# S09_Connectors.net
KiCad netlist of a schematic drawn in Altium Designer
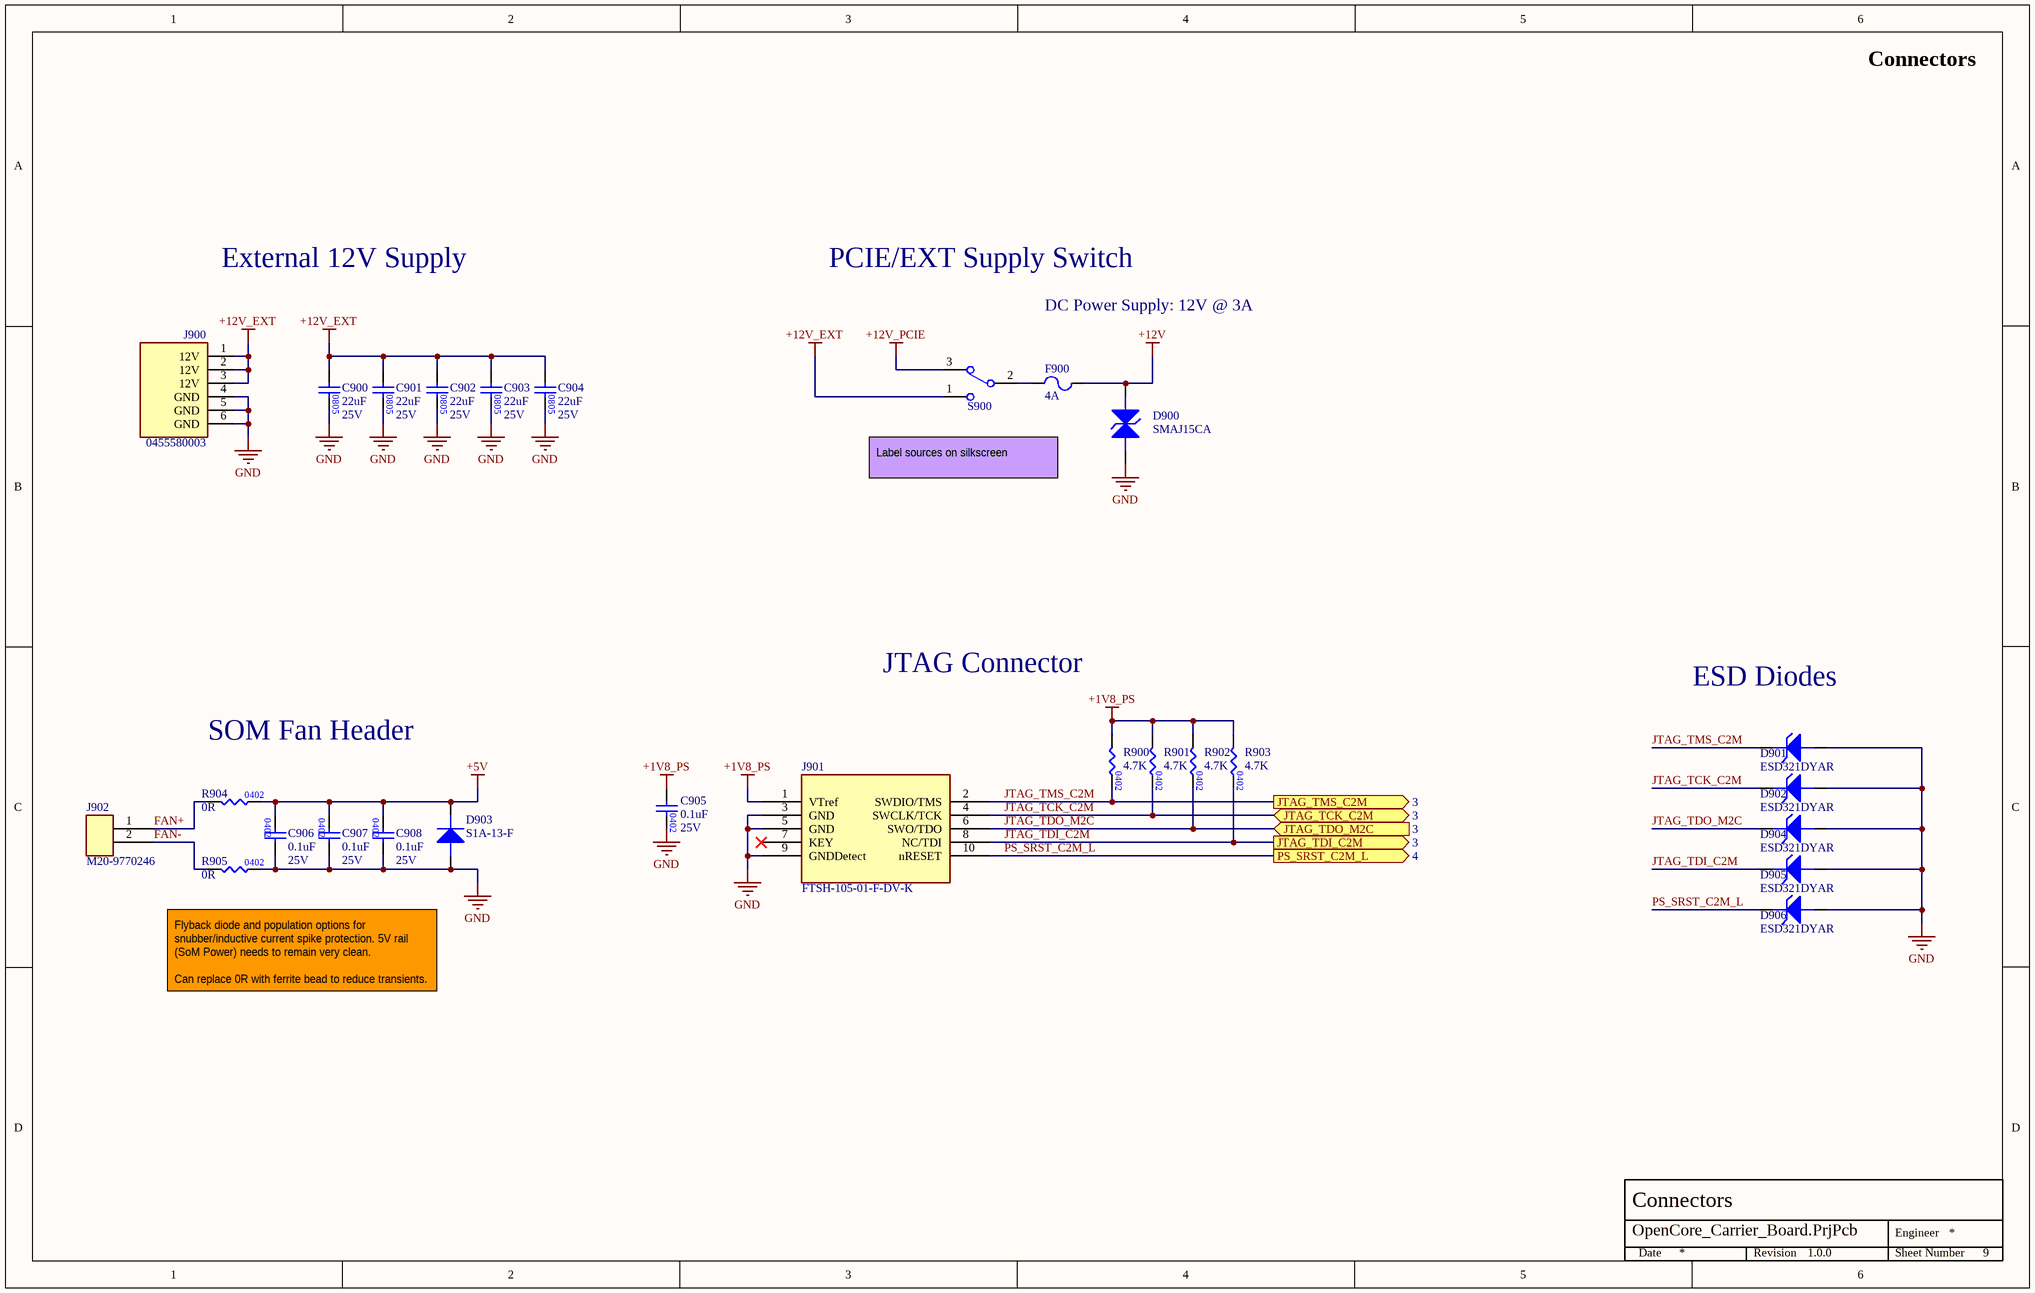
[diagram p0: S09_Connectors.SchDoc]

(export (version "E")
  (design (tool "Eeschema 10.0.6"))
  (components
    (comp (ref "C900")
      (value "22uF")
      (footprint "CAP0805")
      (description "CAP CER 22UF 25V X5R 0805")
      (fields
        (field (name "MANUFACTURER") "Samsung Electro-Mechanics")
        (field (name "TOLERANCE") "20%")
        (field (name "VOLTAGE RATING") "25V")
      )
      (libsource (lib "OpenCore_Sch_Lib") (part "CAP_CL21A226MAYNNNE"))
    )
    (comp (ref "C901")
      (value "22uF")
      (footprint "CAP0805")
      (description "CAP CER 22UF 25V X5R 0805")
      (fields
        (field (name "MANUFACTURER") "Samsung Electro-Mechanics")
        (field (name "TOLERANCE") "20%")
        (field (name "VOLTAGE RATING") "25V")
      )
      (libsource (lib "OpenCore_Sch_Lib") (part "CAP_CL21A226MAYNNNE"))
    )
    (comp (ref "C902")
      (value "22uF")
      (footprint "CAP0805")
      (description "CAP CER 22UF 25V X5R 0805")
      (fields
        (field (name "MANUFACTURER") "Samsung Electro-Mechanics")
        (field (name "TOLERANCE") "20%")
        (field (name "VOLTAGE RATING") "25V")
      )
      (libsource (lib "OpenCore_Sch_Lib") (part "CAP_CL21A226MAYNNNE"))
    )
    (comp (ref "C903")
      (value "22uF")
      (footprint "CAP0805")
      (description "CAP CER 22UF 25V X5R 0805")
      (fields
        (field (name "MANUFACTURER") "Samsung Electro-Mechanics")
        (field (name "TOLERANCE") "20%")
        (field (name "VOLTAGE RATING") "25V")
      )
      (libsource (lib "OpenCore_Sch_Lib") (part "CAP_CL21A226MAYNNNE"))
    )
    (comp (ref "C904")
      (value "22uF")
      (footprint "CAP0805")
      (description "CAP CER 22UF 25V X5R 0805")
      (fields
        (field (name "MANUFACTURER") "Samsung Electro-Mechanics")
        (field (name "TOLERANCE") "20%")
        (field (name "VOLTAGE RATING") "25V")
      )
      (libsource (lib "OpenCore_Sch_Lib") (part "CAP_CL21A226MAYNNNE"))
    )
    (comp (ref "C905")
      (value "0.1uF")
      (footprint "CAP0402")
      (description "CAP CER 0.1UF 25V X5R 0402")
      (fields
        (field (name "MANUFACTURER") "Samsung Electro-Mechanics")
        (field (name "TOLERANCE") "10%")
        (field (name "VOLTAGE RATING") "25V")
      )
      (libsource (lib "OpenCore_Sch_Lib") (part "CAP_CL05A104KA5NNNC"))
    )
    (comp (ref "C906")
      (value "0.1uF")
      (footprint "CAP0402")
      (description "CAP CER 0.1UF 25V X5R 0402")
      (fields
        (field (name "MANUFACTURER") "Samsung Electro-Mechanics")
        (field (name "TOLERANCE") "10%")
        (field (name "VOLTAGE RATING") "25V")
      )
      (libsource (lib "OpenCore_Sch_Lib") (part "CAP_CL05A104KA5NNNC"))
    )
    (comp (ref "C907")
      (value "0.1uF")
      (footprint "CAP0402")
      (description "CAP CER 0.1UF 25V X5R 0402")
      (fields
        (field (name "MANUFACTURER") "Samsung Electro-Mechanics")
        (field (name "TOLERANCE") "10%")
        (field (name "VOLTAGE RATING") "25V")
      )
      (libsource (lib "OpenCore_Sch_Lib") (part "CAP_CL05A104KA5NNNC"))
    )
    (comp (ref "C908")
      (value "0.1uF")
      (footprint "CAP0402")
      (description "CAP CER 0.1UF 25V X5R 0402")
      (fields
        (field (name "MANUFACTURER") "Samsung Electro-Mechanics")
        (field (name "TOLERANCE") "10%")
        (field (name "VOLTAGE RATING") "25V")
      )
      (libsource (lib "OpenCore_Sch_Lib") (part "CAP_CL05A104KA5NNNC"))
    )
    (comp (ref "D900")
      (value "TVS DIODE 15VWM 24.4VC DO214AC")
      (footprint "LITTLEFUSE_DO-2014")
      (description "24.4V Clamp 16.4A Ipp Tvs Diode Surface Mount DO-214AC (SMA)")
      (fields (field (name "MANUFACTURER PART NUMBER") "SMAJ15CA"))
      (libsource (lib "OpenCore_Sch_Lib") (part "SMAJ15CA"))
    )
    (comp (ref "D901")
      (value "ESD321DYAR")
      (footprint "TI_SOD523")
      (description "TVS DIODE 3.6VWM 6.3VC SOT5X3")
      (fields (field (name "MANFACTURER PART NUMBER") "ESD321DYAR"))
      (libsource (lib "OpenCore_Sch_Lib") (part "ESD321DYAR"))
    )
    (comp (ref "D902")
      (value "ESD321DYAR")
      (footprint "TI_SOD523")
      (description "TVS DIODE 3.6VWM 6.3VC SOT5X3")
      (fields (field (name "MANFACTURER PART NUMBER") "ESD321DYAR"))
      (libsource (lib "OpenCore_Sch_Lib") (part "ESD321DYAR"))
    )
    (comp (ref "D903")
      (value "S1A-13-F")
      (footprint "DIODES_SMA")
      (description "Diode 50 V 1A Surface Mount SMA")
      (libsource (lib "OpenCore_Sch_Lib") (part "S1A-13-F"))
    )
    (comp (ref "D904")
      (value "ESD321DYAR")
      (footprint "TI_SOD523")
      (description "TVS DIODE 3.6VWM 6.3VC SOT5X3")
      (fields (field (name "MANFACTURER PART NUMBER") "ESD321DYAR"))
      (libsource (lib "OpenCore_Sch_Lib") (part "ESD321DYAR"))
    )
    (comp (ref "D905")
      (value "ESD321DYAR")
      (footprint "TI_SOD523")
      (description "TVS DIODE 3.6VWM 6.3VC SOT5X3")
      (fields (field (name "MANFACTURER PART NUMBER") "ESD321DYAR"))
      (libsource (lib "OpenCore_Sch_Lib") (part "ESD321DYAR"))
    )
    (comp (ref "D906")
      (value "ESD321DYAR")
      (footprint "TI_SOD523")
      (description "TVS DIODE 3.6VWM 6.3VC SOT5X3")
      (fields (field (name "MANFACTURER PART NUMBER") "ESD321DYAR"))
      (libsource (lib "OpenCore_Sch_Lib") (part "ESD321DYAR"))
    )
    (comp (ref "F900")
      (value "FUSE_4A_0603")
      (footprint "FUSE_0603")
      (description "FUSE SMD 4A 32V")
      (fields (field (name "CURRENT RATING") "4A"))
      (libsource (lib "OpenCore_Sch_Lib") (part "FUSE_4A_0603"))
    )
    (comp (ref "J900")
      (value "0455580003")
      (footprint "0455580003")
      (description "Connector Header Through Hole, Right Angle 6 position 0.165\" (4.20mm)")
      (libsource (lib "OpenCore_Sch_Lib") (part "0455580003"))
    )
    (comp (ref "J901")
      (value "FTSH-105-01-F-DV-K")
      (footprint "FTSH-105-01-F-DV-K-P-TR")
      (description "CONN HEADER SMD 10POS 1.27MM")
      (fields
        (field (name "MANUFACTURER") "Samtec")
        (field (name "MANUFACTURER PART NUMBER 1") "FTSH-105-01-F-DV-K")
      )
      (libsource (lib "OpenCore_Sch_Lib") (part "FTSH-105-01-F-DV-K"))
    )
    (comp (ref "J902")
      (value "M20-9770246")
      (footprint "61300211121")
      (description "CONN HEADER VERT 2POS 2.54MM")
      (libsource (lib "OpenCore_Sch_Lib") (part "M20-9770246"))
    )
    (comp (ref "R900")
      (value "RES_0402")
      (footprint "RES0402")
      (description "RES 4.7K OHM 1% 1/16W 0402")
      (fields
        (field (name "MANUFACTURER") "YAGEO")
        (field (name "MANUFACTURER PART NUMBER") "RC0402FR-074K7L")
        (field (name "RESISTANCE") "4.7K")
      )
      (libsource (lib "OpenCore_Sch_Lib") (part ".RES_RC0402FR-074K7L"))
    )
    (comp (ref "R901")
      (value "RES_0402")
      (footprint "RES0402")
      (description "RES 4.7K OHM 1% 1/16W 0402")
      (fields
        (field (name "MANUFACTURER") "YAGEO")
        (field (name "MANUFACTURER PART NUMBER") "RC0402FR-074K7L")
        (field (name "RESISTANCE") "4.7K")
      )
      (libsource (lib "OpenCore_Sch_Lib") (part ".RES_RC0402FR-074K7L"))
    )
    (comp (ref "R902")
      (value "RES_0402")
      (footprint "RES0402")
      (description "RES 4.7K OHM 1% 1/16W 0402")
      (fields
        (field (name "MANUFACTURER") "YAGEO")
        (field (name "MANUFACTURER PART NUMBER") "RC0402FR-074K7L")
        (field (name "RESISTANCE") "4.7K")
      )
      (libsource (lib "OpenCore_Sch_Lib") (part ".RES_RC0402FR-074K7L"))
    )
    (comp (ref "R903")
      (value "RES_0402")
      (footprint "RES0402")
      (description "RES 4.7K OHM 1% 1/16W 0402")
      (fields
        (field (name "MANUFACTURER") "YAGEO")
        (field (name "MANUFACTURER PART NUMBER") "RC0402FR-074K7L")
        (field (name "RESISTANCE") "4.7K")
      )
      (libsource (lib "OpenCore_Sch_Lib") (part ".RES_RC0402FR-074K7L"))
    )
    (comp (ref "R904")
      (value "RES_0402")
      (footprint "RES0402")
      (description "RES 0 OHM JUMPER 1/16W 0402")
      (fields
        (field (name "MANUFACTURER") "YAGEO")
        (field (name "MANUFACTURER PART NUMBER") "RC0402JR-070RL")
        (field (name "RESISTANCE") "0R")
      )
      (libsource (lib "OpenCore_Sch_Lib") (part ".RES_RC0402JR-070RL"))
    )
    (comp (ref "R905")
      (value "RES_0402")
      (footprint "RES0402")
      (description "RES 0 OHM JUMPER 1/16W 0402")
      (fields
        (field (name "MANUFACTURER") "YAGEO")
        (field (name "MANUFACTURER PART NUMBER") "RC0402JR-070RL")
        (field (name "RESISTANCE") "0R")
      )
      (libsource (lib "OpenCore_Sch_Lib") (part ".RES_RC0402JR-070RL"))
    )
    (comp (ref "S900")
      (value "SW_SLIDE_TOGGLE")
      (footprint "500SSP1S2M2QEA")
      (description "SWITCH SLIDE SPDT 5A 28V")
      (libsource (lib "OpenCore_Sch_Lib") (part "SW_SLIDE_TOGGLE"))
    )
  )
  (nets
    (net (code "1") (name "+1V8_PS") (class "Default")
      (node (ref "C905") (pin "1") (pinfunction "1_1") (pintype "passive"))
      (node (ref "J901") (pin "1") (pinfunction "VTref_1") (pintype "power_in"))
      (node (ref "R900") (pin "1") (pinfunction "1_1") (pintype "passive"))
      (node (ref "R901") (pin "1") (pinfunction "1_1") (pintype "passive"))
      (node (ref "R902") (pin "1") (pinfunction "1_1") (pintype "passive"))
      (node (ref "R903") (pin "1") (pinfunction "1_1") (pintype "passive"))
    )
    (net (code "2") (name "+5V") (class "Default")
      (node (ref "C906") (pin "1") (pinfunction "1_1") (pintype "passive"))
      (node (ref "C907") (pin "1") (pinfunction "1_1") (pintype "passive"))
      (node (ref "C908") (pin "1") (pinfunction "1_1") (pintype "passive"))
      (node (ref "D903") (pin "K") (pinfunction "Cathode_K") (pintype "passive"))
      (node (ref "R904") (pin "2") (pinfunction "2_2") (pintype "passive"))
    )
    (net (code "3") (name "+12V") (class "Default")
      (node (ref "D900") (pin "A") (pinfunction "Anode_A") (pintype "passive"))
      (node (ref "F900") (pin "2") (pinfunction "2_2") (pintype "passive"))
    )
    (net (code "4") (name "+12V_EXT") (class "Default")
      (node (ref "C900") (pin "1") (pinfunction "1_1") (pintype "passive"))
      (node (ref "C901") (pin "1") (pinfunction "1_1") (pintype "passive"))
      (node (ref "C902") (pin "1") (pinfunction "1_1") (pintype "passive"))
      (node (ref "C903") (pin "1") (pinfunction "1_1") (pintype "passive"))
      (node (ref "C904") (pin "1") (pinfunction "1_1") (pintype "passive"))
      (node (ref "J900") (pin "1") (pinfunction "12V_1") (pintype "power_in"))
      (node (ref "J900") (pin "2") (pinfunction "12V_2") (pintype "power_in"))
      (node (ref "J900") (pin "3") (pinfunction "12V_3") (pintype "power_in"))
      (node (ref "S900") (pin "1") (pinfunction "1_1") (pintype "passive"))
    )
    (net (code "5") (name "+12V_PCIE") (class "Default")
      (node (ref "S900") (pin "3") (pinfunction "3_3") (pintype "passive"))
    )
    (net (code "6") (name "/FAN+") (class "Default")
      (node (ref "J902") (pin "1") (pinfunction "1_1") (pintype "passive"))
      (node (ref "R904") (pin "1") (pinfunction "1_1") (pintype "passive"))
    )
    (net (code "7") (name "/FAN-") (class "Default")
      (node (ref "J902") (pin "2") (pinfunction "2_2") (pintype "passive"))
      (node (ref "R905") (pin "1") (pinfunction "1_1") (pintype "passive"))
    )
    (net (code "8") (name "/JTAG_TCK_C2M") (class "Default")
      (node (ref "D902") (pin "K") (pinfunction "Cathode_K") (pintype "passive"))
      (node (ref "J901") (pin "4") (pinfunction "SWCLK/TCK_4") (pintype "passive"))
      (node (ref "R901") (pin "2") (pinfunction "2_2") (pintype "passive"))
    )
    (net (code "9") (name "/JTAG_TDI_C2M") (class "Default")
      (node (ref "D905") (pin "K") (pinfunction "Cathode_K") (pintype "passive"))
      (node (ref "J901") (pin "8") (pinfunction "NC/TDI_8") (pintype "passive"))
      (node (ref "R903") (pin "2") (pinfunction "2_2") (pintype "passive"))
    )
    (net (code "10") (name "/JTAG_TDO_M2C") (class "Default")
      (node (ref "D904") (pin "K") (pinfunction "Cathode_K") (pintype "passive"))
      (node (ref "J901") (pin "6") (pinfunction "SWO/TDO_6") (pintype "passive"))
      (node (ref "R902") (pin "2") (pinfunction "2_2") (pintype "passive"))
    )
    (net (code "11") (name "/JTAG_TMS_C2M") (class "Default")
      (node (ref "D901") (pin "K") (pinfunction "Cathode_K") (pintype "passive"))
      (node (ref "J901") (pin "2") (pinfunction "SWDIO/TMS_2") (pintype "passive"))
      (node (ref "R900") (pin "2") (pinfunction "2_2") (pintype "passive"))
    )
    (net (code "12") (name "/PS_SRST_C2M_L") (class "Default")
      (node (ref "D906") (pin "K") (pinfunction "Cathode_K") (pintype "passive"))
      (node (ref "J901") (pin "10") (pinfunction "nRESET_10") (pintype "passive"))
    )
    (net (code "13") (name "GND") (class "Default")
      (node (ref "C900") (pin "2") (pinfunction "2_2") (pintype "passive"))
      (node (ref "C901") (pin "2") (pinfunction "2_2") (pintype "passive"))
      (node (ref "C902") (pin "2") (pinfunction "2_2") (pintype "passive"))
      (node (ref "C903") (pin "2") (pinfunction "2_2") (pintype "passive"))
      (node (ref "C904") (pin "2") (pinfunction "2_2") (pintype "passive"))
      (node (ref "C905") (pin "2") (pinfunction "2_2") (pintype "passive"))
      (node (ref "C906") (pin "2") (pinfunction "2_2") (pintype "passive"))
      (node (ref "C907") (pin "2") (pinfunction "2_2") (pintype "passive"))
      (node (ref "C908") (pin "2") (pinfunction "2_2") (pintype "passive"))
      (node (ref "D900") (pin "K") (pinfunction "Cathode_K") (pintype "passive"))
      (node (ref "D901") (pin "A") (pinfunction "Anode_A") (pintype "passive"))
      (node (ref "D902") (pin "A") (pinfunction "Anode_A") (pintype "passive"))
      (node (ref "D903") (pin "A") (pinfunction "Anode_A") (pintype "passive"))
      (node (ref "D904") (pin "A") (pinfunction "Anode_A") (pintype "passive"))
      (node (ref "D905") (pin "A") (pinfunction "Anode_A") (pintype "passive"))
      (node (ref "D906") (pin "A") (pinfunction "Anode_A") (pintype "passive"))
      (node (ref "J900") (pin "4") (pinfunction "GND_4") (pintype "power_in"))
      (node (ref "J900") (pin "5") (pinfunction "GND_5") (pintype "power_in"))
      (node (ref "J900") (pin "6") (pinfunction "GND_6") (pintype "power_in"))
      (node (ref "J901") (pin "3") (pinfunction "GND_3") (pintype "power_in"))
      (node (ref "J901") (pin "5") (pinfunction "GND_5") (pintype "power_in"))
      (node (ref "J901") (pin "9") (pinfunction "GNDDetect_9") (pintype "passive"))
      (node (ref "R905") (pin "2") (pinfunction "2_2") (pintype "passive"))
    )
    (net (code "14") (name "Net-(F900-Pad1)") (class "Default")
      (node (ref "F900") (pin "1") (pinfunction "1_1") (pintype "passive"))
      (node (ref "S900") (pin "2") (pinfunction "2_2") (pintype "passive"))
    )
    (net (code "15") (name "unconnected-(J901-KEY-Pad7)") (class "Default")
      (node (ref "J901") (pin "7") (pinfunction "KEY_7") (pintype "passive+no_connect"))
    )
  )
)
